# MP1584_5V.net
KiCad netlist of a schematic drawn in Altium Designer
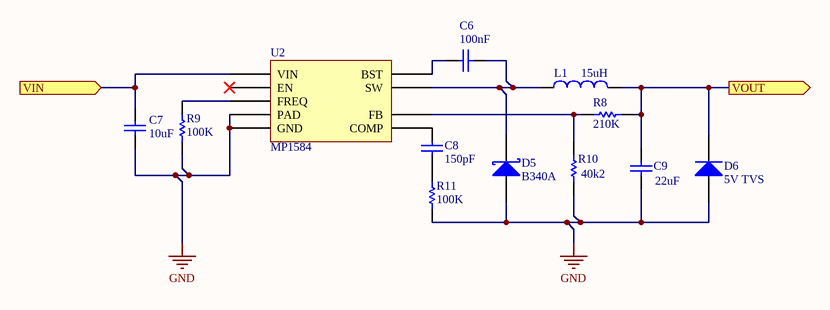
[diagram p0: MP1584_5V.SchDoc]

(export (version "E")
  (design (tool "Eeschema 10.0.6"))
  (components
    (comp (ref "C6")
      (value "100nF")
      (footprint "CAPC0603(1608)100_L")
      (description "CAP 100nF 50V ±5% 0603 (1608 Metric) Thickness 1mm SMD")
      (fields (field (name "TOLERANCE") "Â±5%"))
      (libsource (lib "Altium Content Vault") (part "CMP-1035-02591-1"))
    )
    (comp (ref "C7")
      (value "10uF")
      (footprint "CAPC1210(3225)280_L")
      (description "CAP 10uF 35V ±10% 1210 (3225 Metric) Thickness 2.8mm SMD")
      (fields (field (name "TOLERANCE") "Â±10%"))
      (libsource (lib "Altium Content Vault") (part "CMP-1038-02234-1"))
    )
    (comp (ref "C8")
      (value "150pF")
      (footprint "CAPC0603(1608)100_L")
      (description "CAP 150pF 50V ±5% 0603 (1608 Metric) Thickness 1mm SMD")
      (fields (field (name "TOLERANCE") "Â±5%"))
      (libsource (lib "Altium Content Vault") (part "CMP-1035-01367-1"))
    )
    (comp (ref "C9")
      (value "22uF")
      (footprint "CAPC1210(3225)170_L")
      (description "CAP 22uF 6.3V ±10% 1210 (3225 Metric) Thickness 1.7mm SMD")
      (fields (field (name "TOLERANCE") "Â±10%"))
      (libsource (lib "Altium Content Vault") (part "CMP-1038-02258-1"))
    )
    (comp (ref "D5")
      (value "B340A")
      (footprint "DIOD-SMA-2_V")
      (libsource (lib "Altium Content Vault") (part "CMP-1667-00003-1"))
    )
    (comp (ref "D6")
      (value "5V TVS")
      (footprint "VISH-DO-214AC-2_L")
      (fields
        (field (name "MANUFACTURER") "Vishay Semiconductor")
        (field (name "PARTNUMBER") "SMAJ5.0AHE3/61")
      )
      (libsource (lib "Altium Content Vault") (part "CMP-0548-00062-2"))
    )
    (comp (ref "L1")
      (value "15uH")
      (footprint "0630 Inductor")
      (description "0630 Inductor")
      (fields (field (name "PUBLISHER") "Altium Limited"))
      (libsource (lib "Components") (part "PCC-M0630M"))
    )
    (comp (ref "R8")
      (value "210K")
      (footprint "RESC0603(1608)_L")
      (description "210K 0.1W 1% 0603 (1608 Metric)  SMD")
      (fields (field (name "POWER") "0.1 W") (field (name "TOLERANCE") "1 %"))
      (libsource (lib "Altium Content Vault") (part "CMP-1012-00770-1"))
    )
    (comp (ref "R9")
      (value "100K")
      (footprint "RESC0603(1608)_L")
      (description "100K 0.1W 5% 0603 (1608 Metric)  SMD")
      (fields (field (name "TOLERANCE") "5 %") (field (name "POWER") "0.1 W"))
      (libsource (lib "Altium Content Vault") (part "CMP-1012-00122-1"))
    )
    (comp (ref "R10")
      (value "40k2")
      (footprint "RESC0603(1608)_L")
      (description "40K2 0.1W 1% 0603 (1608 Metric)  SMD")
      (fields (field (name "TOLERANCE") "1 %") (field (name "POWER") "0.1 W"))
      (libsource (lib "Altium Content Vault") (part "CMP-1012-00691-1"))
    )
    (comp (ref "R11")
      (value "100K")
      (footprint "RESC0603(1608)_L")
      (description "100K 0.1W 5% 0603 (1608 Metric)  SMD")
      (fields (field (name "TOLERANCE") "5 %") (field (name "POWER") "0.1 W"))
      (libsource (lib "Altium Content Vault") (part "CMP-1012-00122-1"))
    )
    (comp (ref "U2")
      (value "MP1584")
      (footprint "SOIC8E")
      (description "MP1584 3A, 1.5MHz, 28V Step-Down Converter")
      (libsource (lib "Components") (part "MP1584"))
    )
  )
  (nets
    (net (code "1") (name "/VIN") (class "Default")
      (node (ref "C7") (pin "2") (pinfunction "2_2") (pintype "passive"))
      (node (ref "U2") (pin "7") (pinfunction "VIN_7") (pintype "passive"))
    )
    (net (code "2") (name "/VOUT") (class "Default")
      (node (ref "C9") (pin "2") (pinfunction "2_2") (pintype "passive"))
      (node (ref "D6") (pin "1") (pinfunction "K_1") (pintype "passive"))
      (node (ref "L1") (pin "2") (pinfunction "2_2") (pintype "passive"))
      (node (ref "R8") (pin "2") (pinfunction "2_2") (pintype "passive"))
    )
    (net (code "3") (name "GND") (class "Default")
      (node (ref "C7") (pin "1") (pinfunction "1_1") (pintype "passive"))
      (node (ref "C9") (pin "1") (pinfunction "1_1") (pintype "passive"))
      (node (ref "D5") (pin "1") (pinfunction "A_1") (pintype "passive"))
      (node (ref "D6") (pin "2") (pinfunction "A_2") (pintype "passive"))
      (node (ref "R10") (pin "1") (pinfunction "1_1") (pintype "passive"))
      (node (ref "R11") (pin "1") (pinfunction "1_1") (pintype "passive"))
      (node (ref "R9") (pin "1") (pinfunction "1_1") (pintype "passive"))
      (node (ref "U2") (pin "5") (pinfunction "GND_5") (pintype "passive"))
      (node (ref "U2") (pin "9") (pinfunction "PAD_9") (pintype "passive"))
    )
    (net (code "4") (name "Net-(C8-Pad1)") (class "Default")
      (node (ref "C8") (pin "1") (pinfunction "1_1") (pintype "passive"))
      (node (ref "R11") (pin "2") (pinfunction "2_2") (pintype "passive"))
    )
    (net (code "5") (name "Net-(D5-K)") (class "Default")
      (node (ref "C6") (pin "2") (pinfunction "2_2") (pintype "passive"))
      (node (ref "D5") (pin "2") (pinfunction "K_2") (pintype "passive"))
      (node (ref "L1") (pin "1") (pinfunction "1_1") (pintype "passive"))
      (node (ref "U2") (pin "1") (pinfunction "SW_1") (pintype "passive"))
    )
    (net (code "6") (name "Net-(U2-BST)") (class "Default")
      (node (ref "C6") (pin "1") (pinfunction "1_1") (pintype "passive"))
      (node (ref "U2") (pin "8") (pinfunction "BST_8") (pintype "passive"))
    )
    (net (code "7") (name "Net-(U2-COMP)") (class "Default")
      (node (ref "C8") (pin "2") (pinfunction "2_2") (pintype "passive"))
      (node (ref "U2") (pin "3") (pinfunction "COMP_3") (pintype "passive"))
    )
    (net (code "8") (name "Net-(U2-FB)") (class "Default")
      (node (ref "R10") (pin "2") (pinfunction "2_2") (pintype "passive"))
      (node (ref "R8") (pin "1") (pinfunction "1_1") (pintype "passive"))
      (node (ref "U2") (pin "4") (pinfunction "FB_4") (pintype "passive"))
    )
    (net (code "9") (name "Net-(U2-FREQ)") (class "Default")
      (node (ref "R9") (pin "2") (pinfunction "2_2") (pintype "passive"))
      (node (ref "U2") (pin "6") (pinfunction "FREQ_6") (pintype "passive"))
    )
    (net (code "10") (name "unconnected-(U2-EN-Pad2)") (class "Default")
      (node (ref "U2") (pin "2") (pinfunction "EN_2") (pintype "passive+no_connect"))
    )
  )
)
